# Sony_PSP_USB-C.net
KiCad netlist of a schematic drawn in EAGLE
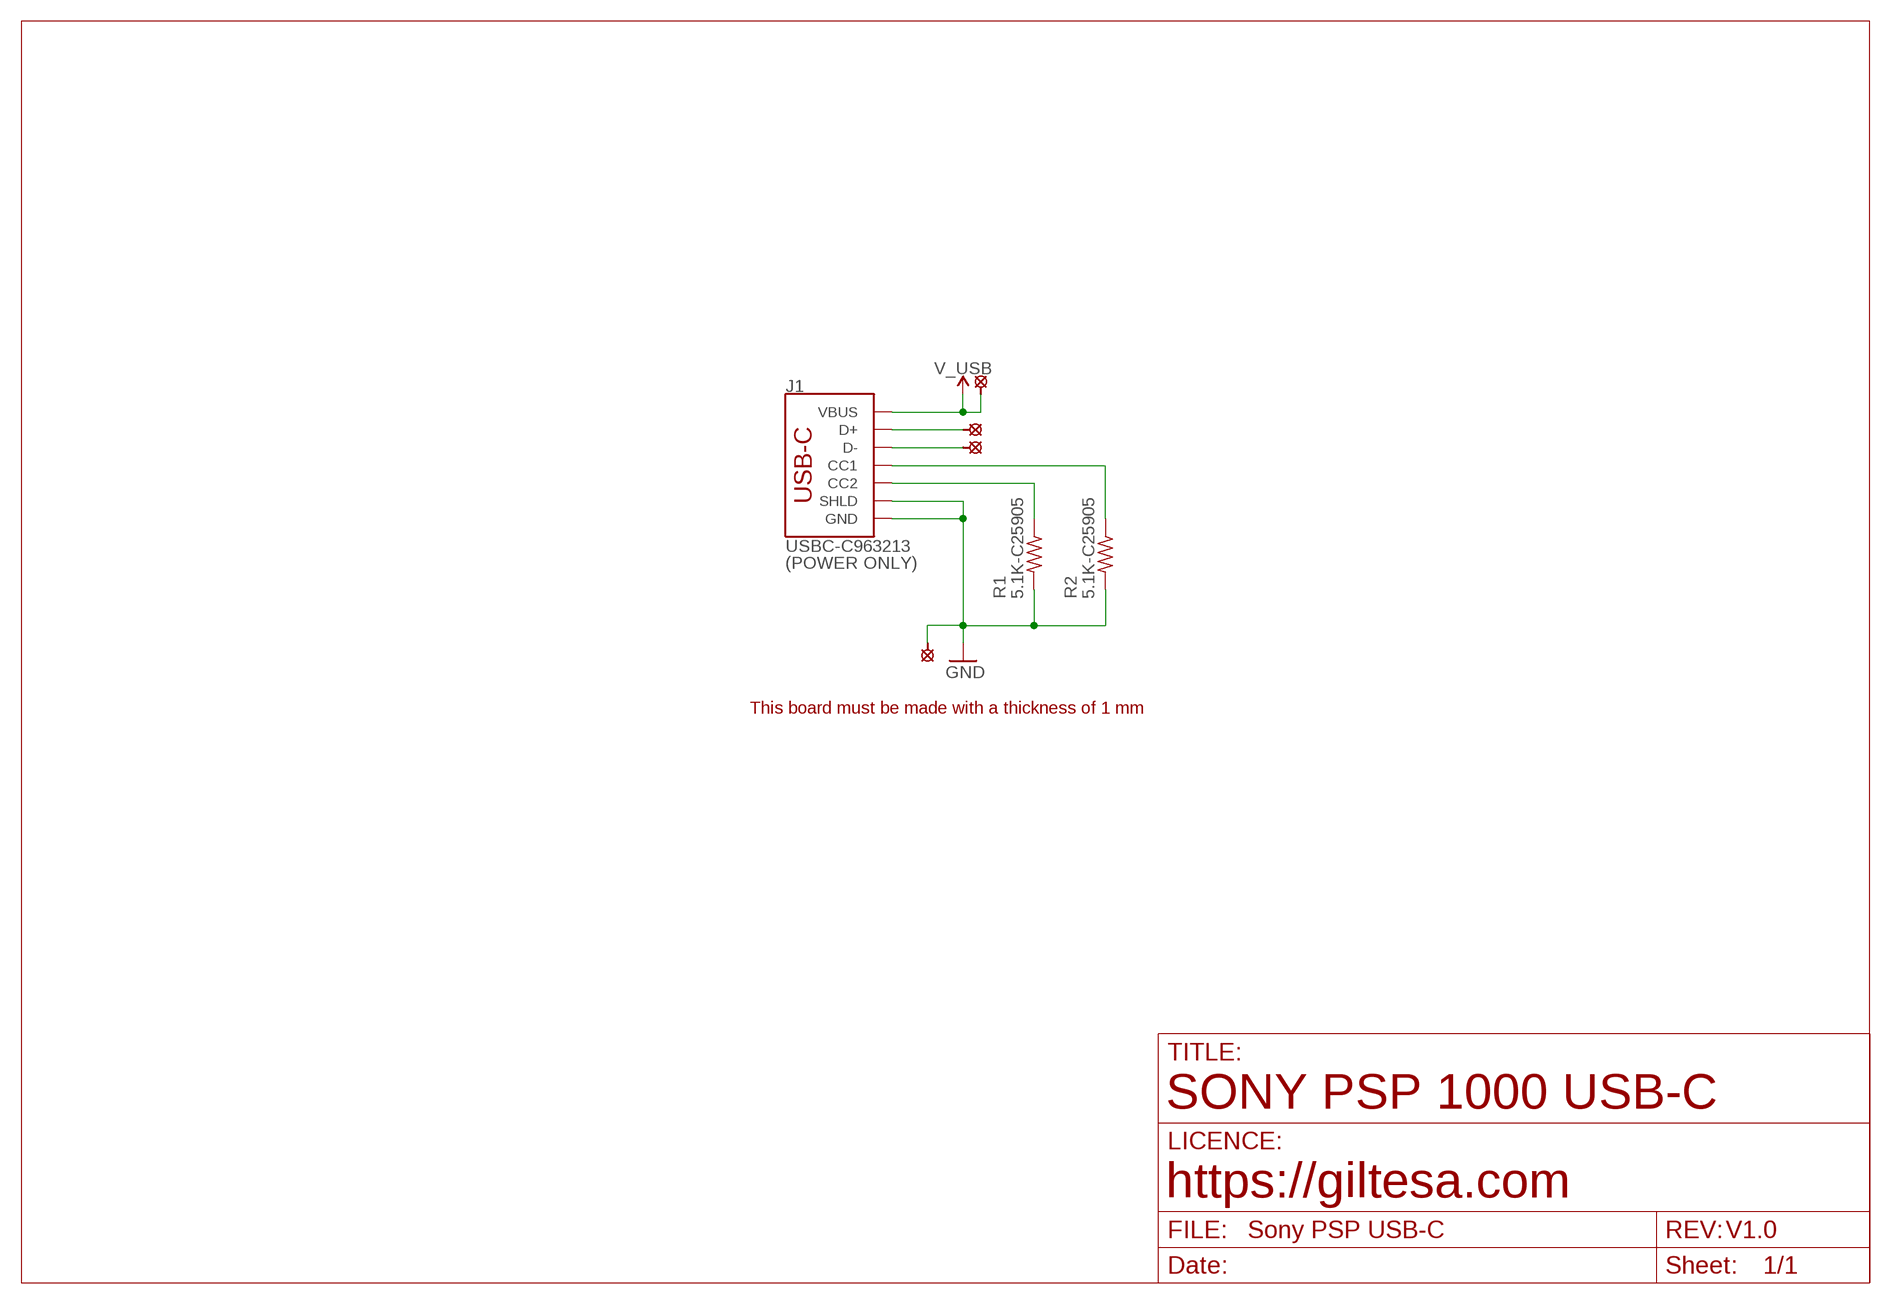
[diagram p0: schematic, sheet 1]

(export (version "E")
  (design (tool "Eeschema 10.0.6"))
  (components
    (comp (ref "J1")
      (value "USBC-C963213")
      (footprint "eagle-import:USB-C_18P_SLIM_GT-USB-7025")
      (libsource (lib "eagle-import") (part "USB-C_16P_DATA_SLIM"))
    )
    (comp (ref "R1")
      (value "5.1K-C25905")
      (footprint "eagle-import:R0402")
      (libsource (lib "eagle-import") (part "R0402"))
    )
    (comp (ref "R2")
      (value "5.1K-C25905")
      (footprint "eagle-import:R0402")
      (libsource (lib "eagle-import") (part "R0402"))
    )
    (comp (ref "U$1")
      (value "SOLDER_PAD_PSP_1000")
      (footprint "eagle-import:PSP_1000_PAD")
      (libsource (lib "eagle-import") (part "SOLDER_PAD_PSP_1000"))
    )
    (comp (ref "U$3")
      (value "SOLDER_PAD_PSP_1000")
      (footprint "eagle-import:PSP_1000_PAD")
      (libsource (lib "eagle-import") (part "SOLDER_PAD_PSP_1000"))
    )
    (comp (ref "U$5")
      (value "SOLDER_PAD-1.3")
      (footprint "eagle-import:SOLDER_PAD_1.3")
      (libsource (lib "eagle-import") (part "SOLDER_PAD-1.3"))
    )
    (comp (ref "U$6")
      (value "SOLDER_PAD-1.3")
      (footprint "eagle-import:SOLDER_PAD_1.3")
      (libsource (lib "eagle-import") (part "SOLDER_PAD-1.3"))
    )
  )
  (nets
    (net (code "1") (name "GND") (class "Default")
      (node (ref "J1") (pin "A1-GND") (pinfunction "GND_A1-GND") (pintype "bidirectional"))
      (node (ref "J1") (pin "A12-GND") (pinfunction "GND_A12-GND") (pintype "bidirectional"))
      (node (ref "J1") (pin "B1-GND") (pinfunction "GND_B1-GND") (pintype "bidirectional"))
      (node (ref "J1") (pin "B12-GND") (pinfunction "GND_B12-GND") (pintype "bidirectional"))
      (node (ref "J1") (pin "GND1") (pinfunction "GND_GND1") (pintype "bidirectional"))
      (node (ref "J1") (pin "GND2") (pinfunction "GND_GND2") (pintype "bidirectional"))
      (node (ref "J1") (pin "SHLD1") (pinfunction "SHLD_SHLD1") (pintype "bidirectional"))
      (node (ref "J1") (pin "SHLD2") (pinfunction "SHLD_SHLD2") (pintype "bidirectional"))
      (node (ref "J1") (pin "SHLD3") (pinfunction "SHLD_SHLD3") (pintype "bidirectional"))
      (node (ref "J1") (pin "SHLD4") (pinfunction "SHLD_SHLD4") (pintype "bidirectional"))
      (node (ref "R1") (pin "2") (pinfunction "2_2") (pintype "passive"))
      (node (ref "R2") (pin "2") (pinfunction "2_2") (pintype "passive"))
      (node (ref "U$1") (pin "1") (pinfunction "P$1_1") (pintype "bidirectional"))
    )
    (net (code "2") (name "Net-(J1-CC1)") (class "Default")
      (node (ref "J1") (pin "A5-CC1") (pinfunction "CC1_A5-CC1") (pintype "bidirectional"))
      (node (ref "R2") (pin "1") (pinfunction "1_1") (pintype "passive"))
    )
    (net (code "3") (name "Net-(J1-CC2)") (class "Default")
      (node (ref "J1") (pin "B5-CC2") (pinfunction "CC2_B5-CC2") (pintype "bidirectional"))
      (node (ref "R1") (pin "1") (pinfunction "1_1") (pintype "passive"))
    )
    (net (code "4") (name "Net-(J1-D+-PadA6-DP1)") (class "Default")
      (node (ref "J1") (pin "A6-DP1") (pinfunction "D+_A6-DP1") (pintype "bidirectional"))
      (node (ref "J1") (pin "B6-DP2") (pinfunction "D+_B6-DP2") (pintype "bidirectional"))
      (node (ref "U$5") (pin "P$1") (pinfunction "P$1_P$1") (pintype "bidirectional"))
    )
    (net (code "5") (name "Net-(J1-D--PadA7-DN1)") (class "Default")
      (node (ref "J1") (pin "A7-DN1") (pinfunction "D-_A7-DN1") (pintype "bidirectional"))
      (node (ref "J1") (pin "B7-DN2") (pinfunction "D-_B7-DN2") (pintype "bidirectional"))
      (node (ref "U$6") (pin "P$1") (pinfunction "P$1_P$1") (pintype "bidirectional"))
    )
    (net (code "6") (name "V_USB") (class "Default")
      (node (ref "J1") (pin "A4-VBUS") (pinfunction "VBUS_A4-VBUS") (pintype "bidirectional"))
      (node (ref "J1") (pin "A9-VBUS") (pinfunction "VBUS_A9-VBUS") (pintype "bidirectional"))
      (node (ref "J1") (pin "B4-VBUS") (pinfunction "VBUS_B4-VBUS") (pintype "bidirectional"))
      (node (ref "J1") (pin "B9-VBUS") (pinfunction "VBUS_B9-VBUS") (pintype "bidirectional"))
      (node (ref "U$3") (pin "1") (pinfunction "P$1_1") (pintype "bidirectional"))
    )
  )
)
